# LEO_COTS_rev0.net
KiCad netlist of a schematic drawn in Altium Designer
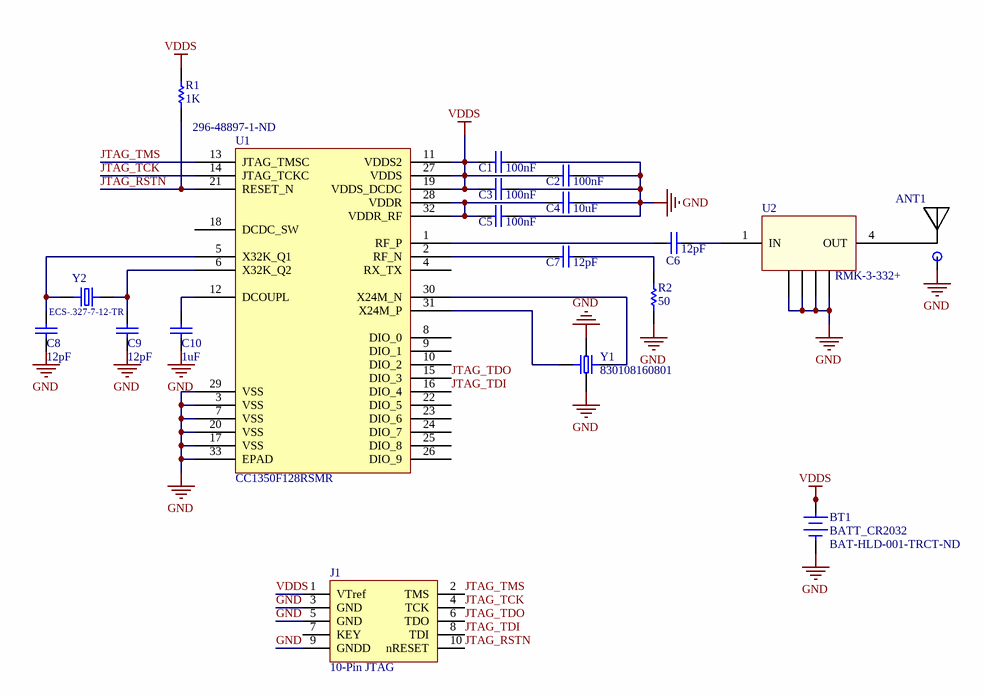
[diagram p0: LEO_COTS_rev0.SchDoc]

(export (version "E")
  (design (tool "Eeschema 10.0.6"))
  (components
    (comp (ref "ANT1")
      (value "ANT")
      (footprint "RESLOOP_OD10_fw15_fl180_sw12_sl15")
      (description "PCB antenna")
      (libsource (lib "LEO_COTS_components") (part "ANT"))
    )
    (comp (ref "BT1")
      (value "BATT_CR2032")
      (footprint "BAT-HLD-001-TR")
      (description "CR2032 Battery Holder")
      (fields (field (name "SUPPLIER PART NUMBER 1") "BAT-HLD-001-TRCT-ND"))
      (libsource (lib "LEO_COTS_components") (part "BATT_CR2032"))
    )
    (comp (ref "C1")
      (value "100nF")
      (footprint "CAPC0603X04N")
      (description "CAP CER 100nF 0201")
      (fields (field (name "Comment") "CAP_0201"))
      (libsource (lib "LEO_COTS_components") (part "CAP_0201"))
    )
    (comp (ref "C2")
      (value "100nF")
      (footprint "CAPC0603X04N")
      (description "CAP CER 100nF 0201")
      (fields (field (name "Comment") "CAP_0201"))
      (libsource (lib "LEO_COTS_components") (part "CAP_0201"))
    )
    (comp (ref "C3")
      (value "100nF")
      (footprint "CAPC0603X04N")
      (description "CAP CER 100nF 0201")
      (fields (field (name "Comment") "CAP_0201"))
      (libsource (lib "LEO_COTS_components") (part "CAP_0201"))
    )
    (comp (ref "C4")
      (value "10uF")
      (footprint "CAPC1608X05N")
      (description "CAP CER 10uF 0603")
      (fields (field (name "Comment") "CAP_0603"))
      (libsource (lib "LEO_COTS_components") (part "CAP_0603"))
    )
    (comp (ref "C5")
      (value "100nF")
      (footprint "CAPC0603X04N")
      (description "CAP CER 100nF 0201")
      (fields (field (name "Comment") "CAP_0201"))
      (libsource (lib "LEO_COTS_components") (part "CAP_0201"))
    )
    (comp (ref "C6")
      (value "12pF")
      (footprint "1608[0603]")
      (description "CAP CER 12pF 0603")
      (fields (field (name "Comment") "CAP"))
      (libsource (lib "LEO_COTS_components") (part "CAP"))
    )
    (comp (ref "C7")
      (value "12pF")
      (footprint "CAPC0603X04N")
      (description "CAP CER 12pF 0201")
      (fields (field (name "Comment") "CAP_0201"))
      (libsource (lib "LEO_COTS_components") (part "CAP_0201"))
    )
    (comp (ref "C8")
      (value "12pF")
      (footprint "CAPC0603X04N")
      (description "CAP CER 12pF 0201")
      (fields (field (name "Comment") "CAP_0201"))
      (libsource (lib "LEO_COTS_components") (part "CAP_0201"))
    )
    (comp (ref "C9")
      (value "12pF")
      (footprint "CAPC0603X04N")
      (description "CAP CER 12pF 0201")
      (fields (field (name "Comment") "CAP_0201"))
      (libsource (lib "LEO_COTS_components") (part "CAP_0201"))
    )
    (comp (ref "C10")
      (value "1uF")
      (footprint "CAPC0603X04N")
      (description "CAP CER 1uF 0201")
      (fields (field (name "Comment") "CAP_0201"))
      (libsource (lib "LEO_COTS_components") (part "CAP_0201"))
    )
    (comp (ref "J1")
      (value "10-Pin JTAG")
      (footprint "FTSH-105-01-F-DV-007-K")
      (description "10-pin JTAG")
      (libsource (lib "LEO_COTS_components") (part "CM10"))
    )
    (comp (ref "R1")
      (value "1K")
      (footprint "CAPC0603X04N")
      (description "RES 1K OHM 0201")
      (fields (field (name "Comment") "RES_0201") (field (name "PUBLISHER") "Altium Limited"))
      (libsource (lib "LEO_COTS_components") (part "Res Semi"))
    )
    (comp (ref "R2")
      (value "50")
      (footprint "CAPC0603X04N")
      (description "RES 50 OHM 0201")
      (fields (field (name "Comment") "RES_0201") (field (name "PUBLISHER") "Altium Limited"))
      (libsource (lib "LEO_COTS_components") (part "Res Semi"))
    )
    (comp (ref "U1")
      (value "CC1350F128RSMR")
      (footprint "QFN40P400X400X100-33N")
      (description "Ultra-Low-Power Dual-Band Wireless MCU")
      (fields (field (name "SUPPLIER PART NUMBER 1") "296-48897-1-ND"))
      (libsource (lib "LEO_COTS_components") (part "CC1350F128RSMR"))
    )
    (comp (ref "U2")
      (value "RMK-3-332+")
      (footprint "RMK-3-331+")
      (description "3x Frequency Multiplier")
      (libsource (lib "LEO_COTS_components") (part "RMK-3-332+"))
    )
    (comp (ref "Y1")
      (value "830108160801")
      (footprint "LFXTAL081608")
      (description "24 MHz crystal")
      (fields (field (name "MP") "ECS-.327-7-12-TR"))
      (libsource (lib "LEO_COTS_components") (part "830108160801"))
    )
    (comp (ref "Y2")
      (value "ECS-.327-7-12-TR")
      (footprint "XTAL_ECS-.327-7-12-TR")
      (description "32.768 kHz SMD Crystal")
      (libsource (lib "LEO_COTS_components") (part "ECS-.327-7-12-TR"))
    )
  )
  (nets
    (net (code "1") (name "/JTAG_RSTN") (class "Default")
      (node (ref "J1") (pin "10") (pinfunction "nRESET_10") (pintype "passive"))
      (node (ref "R1") (pin "1") (pinfunction "1_1") (pintype "passive"))
      (node (ref "U1") (pin "21") (pinfunction "RESET_N_21") (pintype "passive"))
    )
    (net (code "2") (name "/JTAG_TCK") (class "Default")
      (node (ref "J1") (pin "4") (pinfunction "TCK_4") (pintype "passive"))
      (node (ref "U1") (pin "14") (pinfunction "JTAG_TCKC_14") (pintype "passive"))
    )
    (net (code "3") (name "/JTAG_TDI") (class "Default")
      (node (ref "J1") (pin "8") (pinfunction "TDI_8") (pintype "passive"))
      (node (ref "U1") (pin "16") (pinfunction "DIO_4_16") (pintype "passive"))
    )
    (net (code "4") (name "/JTAG_TDO") (class "Default")
      (node (ref "J1") (pin "6") (pinfunction "TDO_6") (pintype "passive"))
      (node (ref "U1") (pin "15") (pinfunction "DIO_3_15") (pintype "passive"))
    )
    (net (code "5") (name "/JTAG_TMS") (class "Default")
      (node (ref "J1") (pin "2") (pinfunction "TMS_2") (pintype "passive"))
      (node (ref "U1") (pin "13") (pinfunction "JTAG_TMSC_13") (pintype "passive"))
    )
    (net (code "6") (name "GND") (class "Default")
      (node (ref "ANT1") (pin "2") (pinfunction "-_2") (pintype "passive"))
      (node (ref "BT1") (pin "N1") (pinfunction "-_N1") (pintype "passive"))
      (node (ref "C1") (pin "1") (pinfunction "1_1") (pintype "passive"))
      (node (ref "C10") (pin "1") (pinfunction "1_1") (pintype "passive"))
      (node (ref "C2") (pin "1") (pinfunction "1_1") (pintype "passive"))
      (node (ref "C3") (pin "1") (pinfunction "1_1") (pintype "passive"))
      (node (ref "C4") (pin "2") (pinfunction "2_2") (pintype "passive"))
      (node (ref "C5") (pin "1") (pinfunction "1_1") (pintype "passive"))
      (node (ref "C8") (pin "1") (pinfunction "1_1") (pintype "passive"))
      (node (ref "C9") (pin "1") (pinfunction "1_1") (pintype "passive"))
      (node (ref "J1") (pin "3") (pinfunction "GND_3") (pintype "passive"))
      (node (ref "J1") (pin "5") (pinfunction "GND_5") (pintype "passive"))
      (node (ref "J1") (pin "9") (pinfunction "GNDD_9") (pintype "passive"))
      (node (ref "R2") (pin "1") (pinfunction "1_1") (pintype "passive"))
      (node (ref "U1") (pin "17") (pinfunction "VSS_17") (pintype "passive"))
      (node (ref "U1") (pin "20") (pinfunction "VSS_20") (pintype "passive"))
      (node (ref "U1") (pin "29") (pinfunction "VSS_29") (pintype "passive"))
      (node (ref "U1") (pin "3") (pinfunction "VSS_3") (pintype "passive"))
      (node (ref "U1") (pin "33") (pinfunction "EPAD_33") (pintype "passive"))
      (node (ref "U1") (pin "7") (pinfunction "VSS_7") (pintype "passive"))
      (node (ref "U2") (pin "2") (pinfunction "2_2") (pintype "passive"))
      (node (ref "U2") (pin "3") (pinfunction "3_3") (pintype "passive"))
      (node (ref "U2") (pin "5") (pinfunction "5_5") (pintype "passive"))
      (node (ref "U2") (pin "6") (pinfunction "6_6") (pintype "passive"))
      (node (ref "Y1") (pin "2") (pinfunction "2_2") (pintype "passive"))
      (node (ref "Y1") (pin "4") (pinfunction "4_4") (pintype "passive"))
    )
    (net (code "7") (name "Net-(ANT1-+)") (class "Default")
      (node (ref "ANT1") (pin "1") (pinfunction "+_1") (pintype "passive"))
      (node (ref "U2") (pin "4") (pinfunction "OUT_4") (pintype "passive"))
    )
    (net (code "8") (name "Net-(C7-Pad1)") (class "Default")
      (node (ref "C7") (pin "1") (pinfunction "1_1") (pintype "passive"))
      (node (ref "R2") (pin "2") (pinfunction "2_2") (pintype "passive"))
    )
    (net (code "9") (name "Net-(U1-DCOUPL)") (class "Default")
      (node (ref "C10") (pin "2") (pinfunction "2_2") (pintype "passive"))
      (node (ref "U1") (pin "12") (pinfunction "DCOUPL_12") (pintype "passive"))
    )
    (net (code "10") (name "Net-(U1-RF_N)") (class "Default")
      (node (ref "C7") (pin "2") (pinfunction "2_2") (pintype "passive"))
      (node (ref "U1") (pin "2") (pinfunction "RF_N_2") (pintype "passive"))
    )
    (net (code "11") (name "Net-(U1-RF_P)") (class "Default")
      (node (ref "C6") (pin "1") (pinfunction "1_1") (pintype "passive"))
      (node (ref "U1") (pin "1") (pinfunction "RF_P_1") (pintype "passive"))
    )
    (net (code "12") (name "Net-(U1-VDDR)") (class "Default")
      (node (ref "C4") (pin "1") (pinfunction "1_1") (pintype "passive"))
      (node (ref "C5") (pin "2") (pinfunction "2_2") (pintype "passive"))
      (node (ref "U1") (pin "28") (pinfunction "VDDR_28") (pintype "passive"))
      (node (ref "U1") (pin "32") (pinfunction "VDDR_RF_32") (pintype "passive"))
    )
    (net (code "13") (name "Net-(U1-X24M_N)") (class "Default")
      (node (ref "U1") (pin "30") (pinfunction "X24M_N_30") (pintype "passive"))
      (node (ref "Y1") (pin "3") (pinfunction "3_3") (pintype "passive"))
    )
    (net (code "14") (name "Net-(U1-X24M_P)") (class "Default")
      (node (ref "U1") (pin "31") (pinfunction "X24M_P_31") (pintype "passive"))
      (node (ref "Y1") (pin "1") (pinfunction "1_1") (pintype "passive"))
    )
    (net (code "15") (name "Net-(U1-X32K_Q1)") (class "Default")
      (node (ref "C8") (pin "2") (pinfunction "2_2") (pintype "passive"))
      (node (ref "U1") (pin "5") (pinfunction "X32K_Q1_5") (pintype "passive"))
      (node (ref "Y2") (pin "1") (pinfunction "1_1") (pintype "passive"))
    )
    (net (code "16") (name "Net-(U1-X32K_Q2)") (class "Default")
      (node (ref "C9") (pin "2") (pinfunction "2_2") (pintype "passive"))
      (node (ref "U1") (pin "6") (pinfunction "X32K_Q2_6") (pintype "passive"))
      (node (ref "Y2") (pin "2") (pinfunction "2_2") (pintype "passive"))
    )
    (net (code "17") (name "Net-(U2-IN)") (class "Default")
      (node (ref "C6") (pin "2") (pinfunction "2_2") (pintype "passive"))
      (node (ref "U2") (pin "1") (pinfunction "IN_1") (pintype "passive"))
    )
    (net (code "18") (name "VDDS") (class "Default")
      (node (ref "BT1") (pin "P1") (pinfunction "+_P1") (pintype "passive"))
      (node (ref "BT1") (pin "P2") (pinfunction "+_P2") (pintype "passive"))
      (node (ref "C1") (pin "2") (pinfunction "2_2") (pintype "passive"))
      (node (ref "C2") (pin "2") (pinfunction "2_2") (pintype "passive"))
      (node (ref "C3") (pin "2") (pinfunction "2_2") (pintype "passive"))
      (node (ref "J1") (pin "1") (pinfunction "VTref_1") (pintype "passive"))
      (node (ref "R1") (pin "2") (pinfunction "2_2") (pintype "passive"))
      (node (ref "U1") (pin "11") (pinfunction "VDDS2_11") (pintype "passive"))
      (node (ref "U1") (pin "19") (pinfunction "VDDS_DCDC_19") (pintype "passive"))
      (node (ref "U1") (pin "27") (pinfunction "VDDS_27") (pintype "passive"))
    )
    (net (code "19") (name "unconnected-(J1-KEY-Pad7)") (class "Default")
      (node (ref "J1") (pin "7") (pinfunction "KEY_7") (pintype "passive"))
    )
    (net (code "20") (name "unconnected-(U1-DCDC_SW-Pad18)") (class "Default")
      (node (ref "U1") (pin "18") (pinfunction "DCDC_SW_18") (pintype "passive"))
    )
    (net (code "21") (name "unconnected-(U1-DIO_0-Pad8)") (class "Default")
      (node (ref "U1") (pin "8") (pinfunction "DIO_0_8") (pintype "passive"))
    )
    (net (code "22") (name "unconnected-(U1-DIO_1-Pad9)") (class "Default")
      (node (ref "U1") (pin "9") (pinfunction "DIO_1_9") (pintype "passive"))
    )
    (net (code "23") (name "unconnected-(U1-DIO_2-Pad10)") (class "Default")
      (node (ref "U1") (pin "10") (pinfunction "DIO_2_10") (pintype "passive"))
    )
    (net (code "24") (name "unconnected-(U1-DIO_5-Pad22)") (class "Default")
      (node (ref "U1") (pin "22") (pinfunction "DIO_5_22") (pintype "passive"))
    )
    (net (code "25") (name "unconnected-(U1-DIO_6-Pad23)") (class "Default")
      (node (ref "U1") (pin "23") (pinfunction "DIO_6_23") (pintype "passive"))
    )
    (net (code "26") (name "unconnected-(U1-DIO_7-Pad24)") (class "Default")
      (node (ref "U1") (pin "24") (pinfunction "DIO_7_24") (pintype "passive"))
    )
    (net (code "27") (name "unconnected-(U1-DIO_8-Pad25)") (class "Default")
      (node (ref "U1") (pin "25") (pinfunction "DIO_8_25") (pintype "passive"))
    )
    (net (code "28") (name "unconnected-(U1-DIO_9-Pad26)") (class "Default")
      (node (ref "U1") (pin "26") (pinfunction "DIO_9_26") (pintype "passive"))
    )
    (net (code "29") (name "unconnected-(U1-RX_TX-Pad4)") (class "Default")
      (node (ref "U1") (pin "4") (pinfunction "RX_TX_4") (pintype "passive"))
    )
  )
)
